# hello.net
KiCad netlist of a schematic drawn in EAGLE
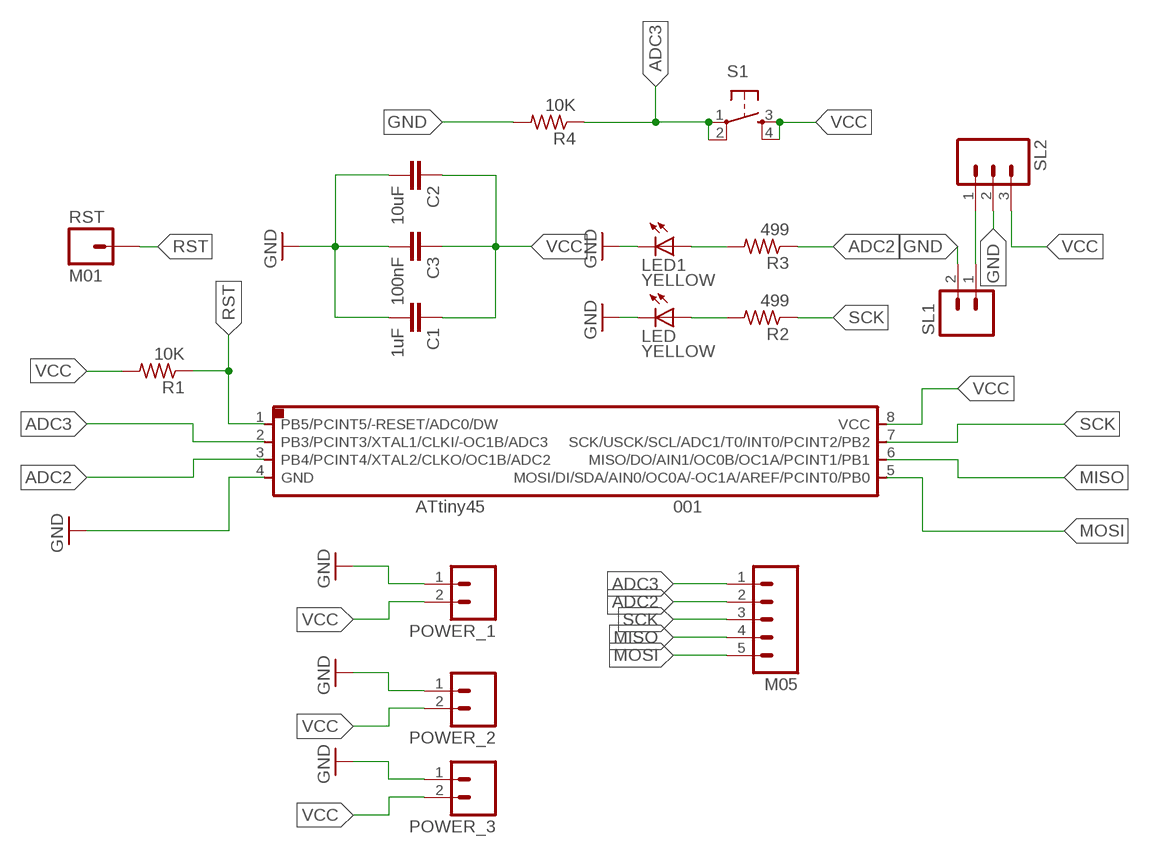
[diagram p0: schematic, sheet 1]

(export (version "E")
  (design (tool "Eeschema 10.0.6"))
  (components
    (comp (ref "001")
      (value "ATTINY45SI")
      (footprint "eagle-import:SOIC8")
      (libsource (lib "eagle-import") (part "ATTINY45SI"))
    )
    (comp (ref "C1")
      (value "1uF")
      (footprint "eagle-import:1206")
      (libsource (lib "eagle-import") (part "CAP1206"))
    )
    (comp (ref "C2")
      (value "10uF")
      (footprint "eagle-import:1206")
      (libsource (lib "eagle-import") (part "CAP1206"))
    )
    (comp (ref "C3")
      (value "100nF")
      (footprint "eagle-import:1206")
      (libsource (lib "eagle-import") (part "CAP1206"))
    )
    (comp (ref "LED")
      (value "YELLOW")
      (footprint "eagle-import:LED1206FAB")
      (libsource (lib "eagle-import") (part "LEDFAB1206"))
    )
    (comp (ref "LED1")
      (value "YELLOW")
      (footprint "eagle-import:LED1206FAB")
      (libsource (lib "eagle-import") (part "LEDFAB1206"))
    )
    (comp (ref "M05")
      (value "M05")
      (footprint "eagle-import:05P")
      (libsource (lib "eagle-import") (part "M05"))
    )
    (comp (ref "POWER_1")
      (value "M02")
      (footprint "eagle-import:02P")
      (libsource (lib "eagle-import") (part "M02"))
    )
    (comp (ref "POWER_2")
      (value "M02")
      (footprint "eagle-import:02P")
      (libsource (lib "eagle-import") (part "M02"))
    )
    (comp (ref "POWER_3")
      (value "M02")
      (footprint "eagle-import:02P")
      (libsource (lib "eagle-import") (part "M02"))
    )
    (comp (ref "R1")
      (value "10K")
      (footprint "eagle-import:R1206FAB")
      (libsource (lib "eagle-import") (part "RES-US1206FAB"))
    )
    (comp (ref "R2")
      (value "499")
      (footprint "eagle-import:R1206FAB")
      (libsource (lib "eagle-import") (part "fablab_RES-US1206FAB"))
    )
    (comp (ref "R3")
      (value "499")
      (footprint "eagle-import:R1206FAB")
      (libsource (lib "eagle-import") (part "fablab_RES-US1206FAB"))
    )
    (comp (ref "R4")
      (value "10K")
      (footprint "eagle-import:R1206FAB")
      (libsource (lib "eagle-import") (part "fablab_RES-US1206FAB"))
    )
    (comp (ref "RST")
      (value "M01")
      (footprint "eagle-import:1X01_LONGPAD")
      (libsource (lib "eagle-import") (part "M01PTH_LONGPAD"))
    )
    (comp (ref "S1")
      (value "6MM_SWITCH6MM_SWITCH")
      (footprint "eagle-import:6MM_SWITCH")
      (libsource (lib "eagle-import") (part "6MM_SWITCH6MM_SWITCH"))
    )
    (comp (ref "SL1")
      (value "M02")
      (footprint "eagle-import:02P")
      (libsource (lib "eagle-import") (part "con-amp-quick_125_M02"))
    )
    (comp (ref "SL2")
      (value "M03")
      (footprint "eagle-import:03P")
      (libsource (lib "eagle-import") (part "M03"))
    )
  )
  (nets
    (net (code "1") (name "ADC2") (class "Default")
      (node (ref "001") (pin "3") (pinfunction "PB4/PCINT4/XTAL2/CLKO/OC1B/ADC2_3") (pintype "bidirectional"))
      (node (ref "M05") (pin "2") (pinfunction "2_2") (pintype "passive"))
      (node (ref "R3") (pin "1") (pinfunction "1_1") (pintype "passive"))
    )
    (net (code "2") (name "ADC3") (class "Default")
      (node (ref "001") (pin "2") (pinfunction "PB3/PCINT3/XTAL1/CLKI/-OC1B/ADC3_2") (pintype "bidirectional"))
      (node (ref "M05") (pin "1") (pinfunction "1_1") (pintype "passive"))
      (node (ref "R4") (pin "1") (pinfunction "1_1") (pintype "passive"))
      (node (ref "S1") (pin "1") (pinfunction "P_1") (pintype "passive"))
      (node (ref "S1") (pin "2") (pinfunction "P1_2") (pintype "passive"))
    )
    (net (code "3") (name "GND") (class "Default")
      (node (ref "001") (pin "4") (pinfunction "GND_4") (pintype "bidirectional"))
      (node (ref "C1") (pin "2") (pinfunction "2_2") (pintype "passive"))
      (node (ref "C2") (pin "2") (pinfunction "2_2") (pintype "passive"))
      (node (ref "C3") (pin "2") (pinfunction "2_2") (pintype "passive"))
      (node (ref "LED") (pin "2") (pinfunction "C_2") (pintype "passive"))
      (node (ref "LED1") (pin "2") (pinfunction "C_2") (pintype "passive"))
      (node (ref "POWER_1") (pin "1") (pinfunction "1_1") (pintype "passive"))
      (node (ref "POWER_2") (pin "1") (pinfunction "1_1") (pintype "passive"))
      (node (ref "POWER_3") (pin "1") (pinfunction "1_1") (pintype "passive"))
      (node (ref "R4") (pin "2") (pinfunction "2_2") (pintype "passive"))
      (node (ref "SL1") (pin "2") (pinfunction "2_2") (pintype "passive"))
      (node (ref "SL2") (pin "2") (pinfunction "2_2") (pintype "passive"))
    )
    (net (code "4") (name "MISO") (class "Default")
      (node (ref "001") (pin "6") (pinfunction "MISO/DO/AIN1/OC0B/OC1A/PCINT1/PB1_6") (pintype "bidirectional"))
      (node (ref "M05") (pin "4") (pinfunction "4_4") (pintype "passive"))
    )
    (net (code "5") (name "MOSI") (class "Default")
      (node (ref "001") (pin "5") (pinfunction "MOSI/DI/SDA/AIN0/OC0A/-OC1A/AREF/PCINT0/PB0_5") (pintype "bidirectional"))
      (node (ref "M05") (pin "5") (pinfunction "5_5") (pintype "passive"))
    )
    (net (code "6") (name "Net-(LED-A)") (class "Default")
      (node (ref "LED") (pin "1") (pinfunction "A_1") (pintype "passive"))
      (node (ref "R2") (pin "2") (pinfunction "2_2") (pintype "passive"))
    )
    (net (code "7") (name "Net-(LED1-A)") (class "Default")
      (node (ref "LED1") (pin "1") (pinfunction "A_1") (pintype "passive"))
      (node (ref "R3") (pin "2") (pinfunction "2_2") (pintype "passive"))
    )
    (net (code "8") (name "Net-(SL1-Pad1)") (class "Default")
      (node (ref "SL1") (pin "1") (pinfunction "1_1") (pintype "passive"))
      (node (ref "SL2") (pin "1") (pinfunction "1_1") (pintype "passive"))
    )
    (net (code "9") (name "RST") (class "Default")
      (node (ref "001") (pin "1") (pinfunction "PB5/PCINT5/-RESET/ADC0/DW_1") (pintype "bidirectional"))
      (node (ref "R1") (pin "1") (pinfunction "1_1") (pintype "passive"))
      (node (ref "RST") (pin "1") (pinfunction "1_1") (pintype "passive"))
    )
    (net (code "10") (name "SCK") (class "Default")
      (node (ref "001") (pin "7") (pinfunction "SCK/USCK/SCL/ADC1/T0/INT0/PCINT2/PB2_7") (pintype "bidirectional"))
      (node (ref "M05") (pin "3") (pinfunction "3_3") (pintype "passive"))
      (node (ref "R2") (pin "1") (pinfunction "1_1") (pintype "passive"))
    )
    (net (code "11") (name "VCC") (class "Default")
      (node (ref "001") (pin "8") (pinfunction "VCC_8") (pintype "bidirectional"))
      (node (ref "C1") (pin "1") (pinfunction "1_1") (pintype "passive"))
      (node (ref "C2") (pin "1") (pinfunction "1_1") (pintype "passive"))
      (node (ref "C3") (pin "1") (pinfunction "1_1") (pintype "passive"))
      (node (ref "POWER_1") (pin "2") (pinfunction "2_2") (pintype "passive"))
      (node (ref "POWER_2") (pin "2") (pinfunction "2_2") (pintype "passive"))
      (node (ref "POWER_3") (pin "2") (pinfunction "2_2") (pintype "passive"))
      (node (ref "R1") (pin "2") (pinfunction "2_2") (pintype "passive"))
      (node (ref "S1") (pin "3") (pinfunction "S_3") (pintype "passive"))
      (node (ref "S1") (pin "4") (pinfunction "S1_4") (pintype "passive"))
      (node (ref "SL2") (pin "3") (pinfunction "3_3") (pintype "passive"))
    )
  )
)
